# wemos_gpio.net
KiCad netlist of a schematic drawn in EAGLE
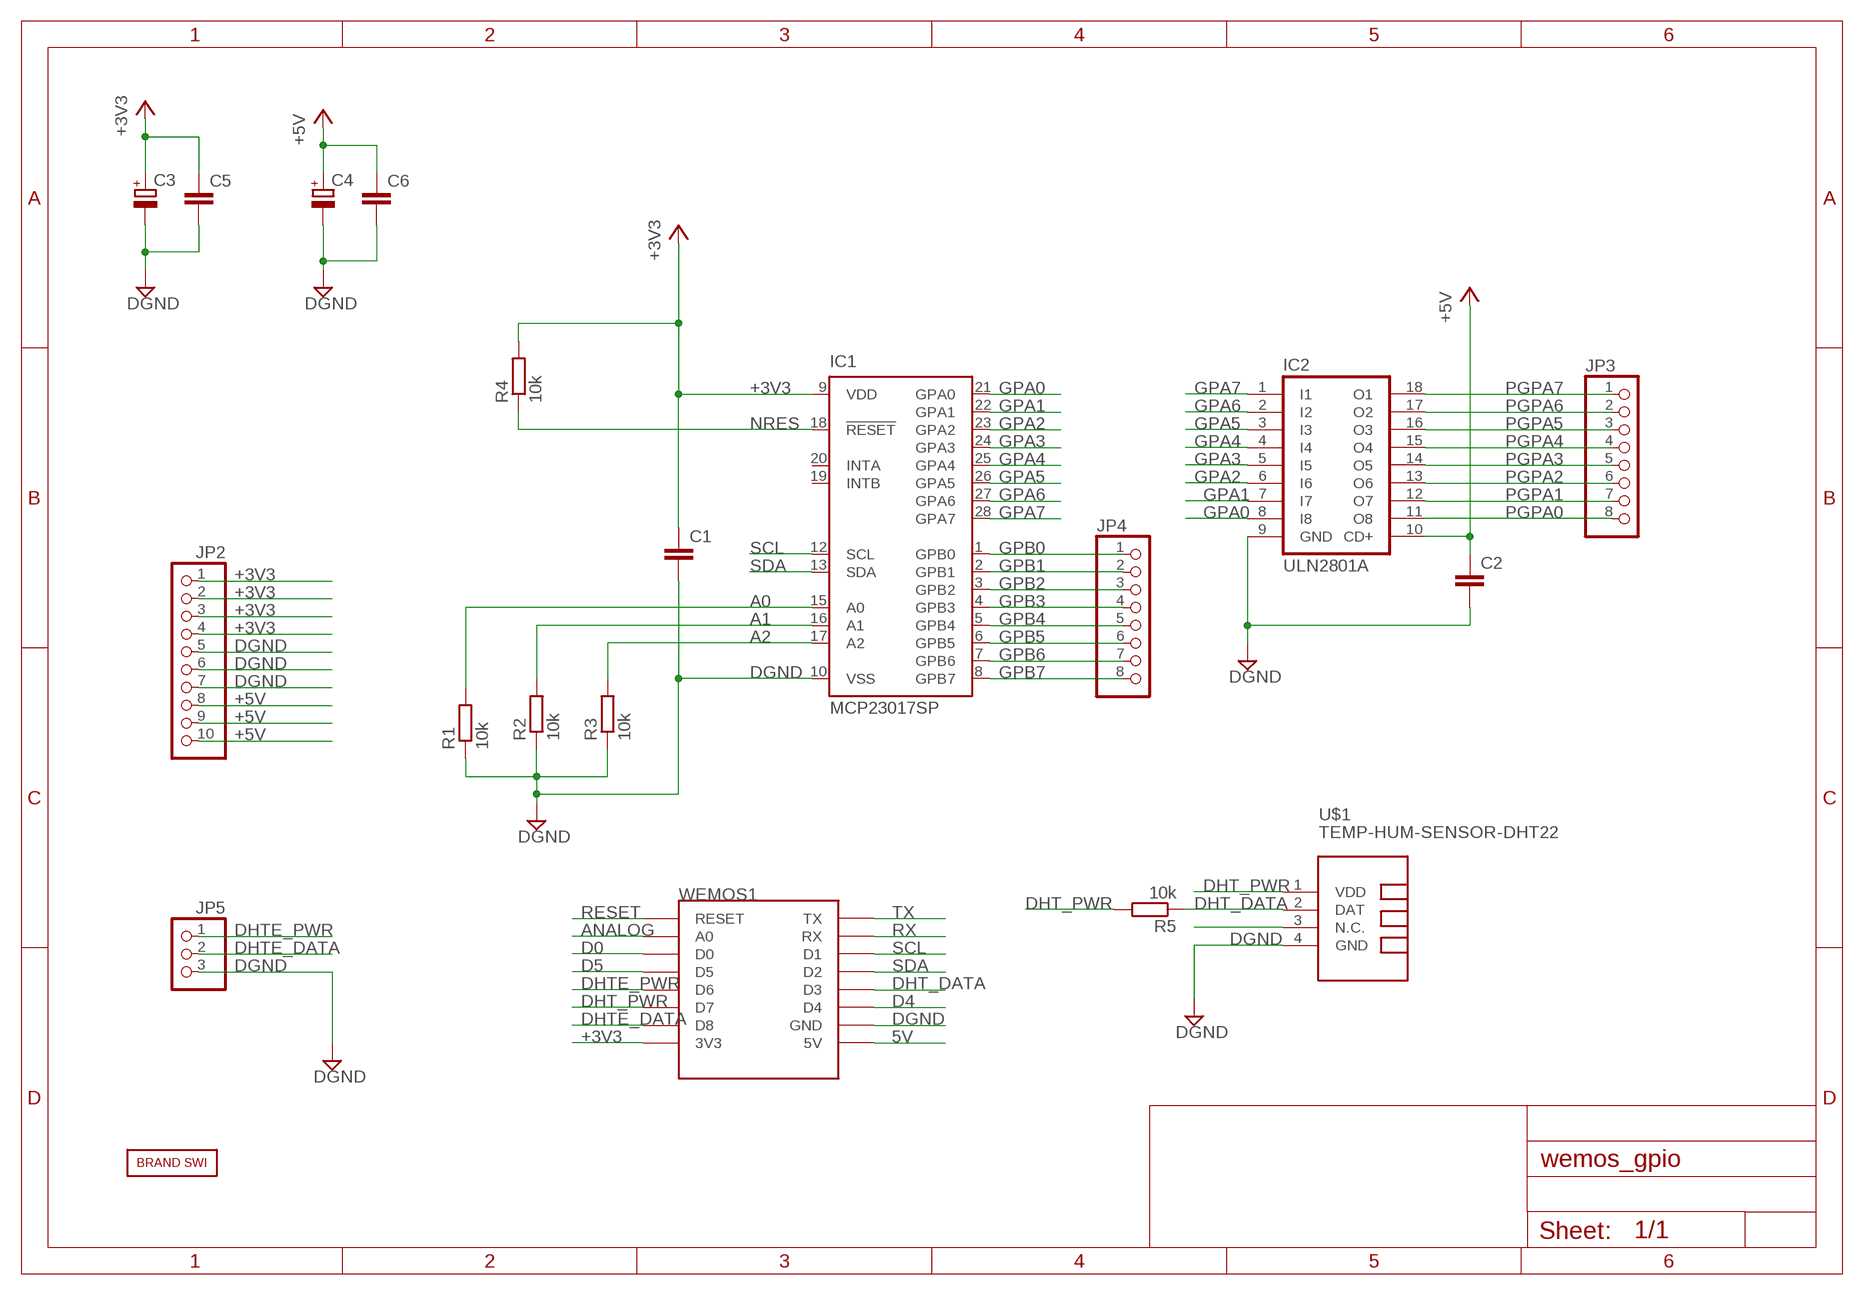
[diagram p0: schematic, sheet 1]

(export (version "E")
  (design (tool "Eeschema 10.0.6"))
  (components
    (comp (ref "C1")
      (value "C-EUC1210")
      (footprint "eagle-import:C1210")
      (libsource (lib "eagle-import") (part "C-EUC1210"))
    )
    (comp (ref "C2")
      (value "C-EUC1210")
      (footprint "eagle-import:C1210")
      (libsource (lib "eagle-import") (part "C-EUC1210"))
    )
    (comp (ref "C3")
      (value "CPOL-EUTT5D7")
      (footprint "eagle-import:TT5D7")
      (libsource (lib "eagle-import") (part "CPOL-EUTT5D7"))
    )
    (comp (ref "C4")
      (value "CPOL-EUTT5D7")
      (footprint "eagle-import:TT5D7")
      (libsource (lib "eagle-import") (part "CPOL-EUTT5D7"))
    )
    (comp (ref "C5")
      (value "C-EUC1210")
      (footprint "eagle-import:C1210")
      (libsource (lib "eagle-import") (part "C-EUC1210"))
    )
    (comp (ref "C6")
      (value "C-EUC1210")
      (footprint "eagle-import:C1210")
      (libsource (lib "eagle-import") (part "C-EUC1210"))
    )
    (comp (ref "IC1")
      (value "MCP23017SP")
      (footprint "eagle-import:DIL28-3")
      (fields (field (name "MF") "MICROCHIP") (field (name "MPN") "MCP23017-E/SP"))
      (libsource (lib "eagle-import") (part "MCP23017SP"))
    )
    (comp (ref "IC2")
      (value "ULN2801A")
      (footprint "eagle-import:DIL18")
      (libsource (lib "eagle-import") (part "ULN2801A"))
    )
    (comp (ref "JP2")
      (value "PINHD-1X10")
      (footprint "eagle-import:1X10")
      (libsource (lib "eagle-import") (part "PINHD-1X10"))
    )
    (comp (ref "JP3")
      (value "PINHD-1X8")
      (footprint "eagle-import:1X08")
      (libsource (lib "eagle-import") (part "PINHD-1X8"))
    )
    (comp (ref "JP4")
      (value "PINHD-1X8")
      (footprint "eagle-import:1X08")
      (libsource (lib "eagle-import") (part "PINHD-1X8"))
    )
    (comp (ref "JP5")
      (value "PINHD-1X3")
      (footprint "eagle-import:1X03")
      (libsource (lib "eagle-import") (part "PINHD-1X3"))
    )
    (comp (ref "R1")
      (value "10k")
      (footprint "eagle-import:M1206")
      (libsource (lib "eagle-import") (part "R-EU_M1206"))
    )
    (comp (ref "R2")
      (value "10k")
      (footprint "eagle-import:M1206")
      (libsource (lib "eagle-import") (part "R-EU_M1206"))
    )
    (comp (ref "R3")
      (value "10k")
      (footprint "eagle-import:M1206")
      (libsource (lib "eagle-import") (part "R-EU_M1206"))
    )
    (comp (ref "R4")
      (value "10k")
      (footprint "eagle-import:M1206")
      (libsource (lib "eagle-import") (part "R-EU_M1206"))
    )
    (comp (ref "R5")
      (value "10k")
      (footprint "eagle-import:M1206")
      (libsource (lib "eagle-import") (part "R-EU_M1206"))
    )
    (comp (ref "U$1")
      (value "TEMP-HUM-SENSOR-DHT22")
      (footprint "eagle-import:TEMP-HUM-SENSOR-DHT22")
      (libsource (lib "eagle-import") (part "TEMP-HUM-SENSOR-DHT22"))
    )
    (comp (ref "U$2")
      (value "BRAND_SWI5X7")
      (footprint "eagle-import:BRAND_SWI_5X7")
      (libsource (lib "eagle-import") (part "BRAND_SWI5X7"))
    )
    (comp (ref "WEMOS1")
      (value "WEMOS-D1-MINI")
      (footprint "eagle-import:WEMOS-D1-MINI")
      (libsource (lib "eagle-import") (part "WEMOS-D1-MINI"))
    )
  )
  (nets
    (net (code "1") (name "+3V3") (class "Default")
      (node (ref "C1") (pin "1") (pinfunction "1_1") (pintype "passive"))
      (node (ref "C3") (pin "+") (pinfunction "+_+") (pintype "passive"))
      (node (ref "C5") (pin "1") (pinfunction "1_1") (pintype "passive"))
      (node (ref "IC1") (pin "9") (pinfunction "VDD_9") (pintype "power_in"))
      (node (ref "JP2") (pin "1") (pinfunction "1_1") (pintype "passive"))
      (node (ref "JP2") (pin "2") (pinfunction "2_2") (pintype "passive"))
      (node (ref "JP2") (pin "3") (pinfunction "3_3") (pintype "passive"))
      (node (ref "JP2") (pin "4") (pinfunction "4_4") (pintype "passive"))
      (node (ref "R4") (pin "2") (pinfunction "2_2") (pintype "passive"))
      (node (ref "WEMOS1") (pin "3V3") (pinfunction "3V3_3V3") (pintype "bidirectional"))
    )
    (net (code "2") (name "+5V") (class "Default")
      (node (ref "C2") (pin "1") (pinfunction "1_1") (pintype "passive"))
      (node (ref "C4") (pin "+") (pinfunction "+_+") (pintype "passive"))
      (node (ref "C6") (pin "1") (pinfunction "1_1") (pintype "passive"))
      (node (ref "IC2") (pin "10") (pinfunction "CD+_10") (pintype "passive"))
      (node (ref "JP2") (pin "10") (pinfunction "10_10") (pintype "passive"))
      (node (ref "JP2") (pin "8") (pinfunction "8_8") (pintype "passive"))
      (node (ref "JP2") (pin "9") (pinfunction "9_9") (pintype "passive"))
    )
    (net (code "3") (name "/5V") (class "Default")
      (node (ref "WEMOS1") (pin "5V") (pinfunction "5V_5V") (pintype "bidirectional"))
    )
    (net (code "4") (name "/A0") (class "Default")
      (node (ref "IC1") (pin "15") (pinfunction "A0_15") (pintype "input"))
      (node (ref "R1") (pin "2") (pinfunction "2_2") (pintype "passive"))
    )
    (net (code "5") (name "/A1") (class "Default")
      (node (ref "IC1") (pin "16") (pinfunction "A1_16") (pintype "input"))
      (node (ref "R2") (pin "2") (pinfunction "2_2") (pintype "passive"))
    )
    (net (code "6") (name "/A2") (class "Default")
      (node (ref "IC1") (pin "17") (pinfunction "A2_17") (pintype "input"))
      (node (ref "R3") (pin "2") (pinfunction "2_2") (pintype "passive"))
    )
    (net (code "7") (name "/ANALOG") (class "Default")
      (node (ref "WEMOS1") (pin "A0") (pinfunction "A0_A0") (pintype "bidirectional"))
    )
    (net (code "8") (name "/D0") (class "Default")
      (node (ref "WEMOS1") (pin "D0") (pinfunction "D0_D0") (pintype "bidirectional"))
    )
    (net (code "9") (name "/D4") (class "Default")
      (node (ref "WEMOS1") (pin "D4") (pinfunction "D4_D4") (pintype "bidirectional"))
    )
    (net (code "10") (name "/D5") (class "Default")
      (node (ref "WEMOS1") (pin "D5") (pinfunction "D5_D5") (pintype "bidirectional"))
    )
    (net (code "11") (name "/DHTE_DATA") (class "Default")
      (node (ref "JP5") (pin "2") (pinfunction "2_2") (pintype "passive"))
      (node (ref "WEMOS1") (pin "D8") (pinfunction "D8_D8") (pintype "bidirectional"))
    )
    (net (code "12") (name "/DHTE_PWR") (class "Default")
      (node (ref "JP5") (pin "1") (pinfunction "1_1") (pintype "passive"))
      (node (ref "WEMOS1") (pin "D6") (pinfunction "D6_D6") (pintype "bidirectional"))
    )
    (net (code "13") (name "/DHT_DATA") (class "Default")
      (node (ref "R5") (pin "1") (pinfunction "1_1") (pintype "passive"))
      (node (ref "U$1") (pin "2") (pinfunction "DAT_2") (pintype "bidirectional"))
      (node (ref "WEMOS1") (pin "D3") (pinfunction "D3_D3") (pintype "bidirectional"))
    )
    (net (code "14") (name "/DHT_PWR") (class "Default")
      (node (ref "R5") (pin "2") (pinfunction "2_2") (pintype "passive"))
      (node (ref "U$1") (pin "1") (pinfunction "VDD_1") (pintype "power_in"))
      (node (ref "WEMOS1") (pin "D7") (pinfunction "D7_D7") (pintype "bidirectional"))
    )
    (net (code "15") (name "/GPA0") (class "Default")
      (node (ref "IC1") (pin "21") (pinfunction "GPA0_21") (pintype "bidirectional"))
      (node (ref "IC2") (pin "8") (pinfunction "I8_8") (pintype "input"))
    )
    (net (code "16") (name "/GPA1") (class "Default")
      (node (ref "IC1") (pin "22") (pinfunction "GPA1_22") (pintype "bidirectional"))
      (node (ref "IC2") (pin "7") (pinfunction "I7_7") (pintype "input"))
    )
    (net (code "17") (name "/GPA2") (class "Default")
      (node (ref "IC1") (pin "23") (pinfunction "GPA2_23") (pintype "bidirectional"))
      (node (ref "IC2") (pin "6") (pinfunction "I6_6") (pintype "input"))
    )
    (net (code "18") (name "/GPA3") (class "Default")
      (node (ref "IC1") (pin "24") (pinfunction "GPA3_24") (pintype "bidirectional"))
      (node (ref "IC2") (pin "5") (pinfunction "I5_5") (pintype "input"))
    )
    (net (code "19") (name "/GPA4") (class "Default")
      (node (ref "IC1") (pin "25") (pinfunction "GPA4_25") (pintype "bidirectional"))
      (node (ref "IC2") (pin "4") (pinfunction "I4_4") (pintype "input"))
    )
    (net (code "20") (name "/GPA5") (class "Default")
      (node (ref "IC1") (pin "26") (pinfunction "GPA5_26") (pintype "bidirectional"))
      (node (ref "IC2") (pin "3") (pinfunction "I3_3") (pintype "input"))
    )
    (net (code "21") (name "/GPA6") (class "Default")
      (node (ref "IC1") (pin "27") (pinfunction "GPA6_27") (pintype "bidirectional"))
      (node (ref "IC2") (pin "2") (pinfunction "I2_2") (pintype "input"))
    )
    (net (code "22") (name "/GPA7") (class "Default")
      (node (ref "IC1") (pin "28") (pinfunction "GPA7_28") (pintype "bidirectional"))
      (node (ref "IC2") (pin "1") (pinfunction "I1_1") (pintype "input"))
    )
    (net (code "23") (name "/GPB0") (class "Default")
      (node (ref "IC1") (pin "1") (pinfunction "GPB0_1") (pintype "bidirectional"))
      (node (ref "JP4") (pin "1") (pinfunction "1_1") (pintype "passive"))
    )
    (net (code "24") (name "/GPB1") (class "Default")
      (node (ref "IC1") (pin "2") (pinfunction "GPB1_2") (pintype "bidirectional"))
      (node (ref "JP4") (pin "2") (pinfunction "2_2") (pintype "passive"))
    )
    (net (code "25") (name "/GPB2") (class "Default")
      (node (ref "IC1") (pin "3") (pinfunction "GPB2_3") (pintype "bidirectional"))
      (node (ref "JP4") (pin "3") (pinfunction "3_3") (pintype "passive"))
    )
    (net (code "26") (name "/GPB3") (class "Default")
      (node (ref "IC1") (pin "4") (pinfunction "GPB3_4") (pintype "bidirectional"))
      (node (ref "JP4") (pin "4") (pinfunction "4_4") (pintype "passive"))
    )
    (net (code "27") (name "/GPB4") (class "Default")
      (node (ref "IC1") (pin "5") (pinfunction "GPB4_5") (pintype "bidirectional"))
      (node (ref "JP4") (pin "5") (pinfunction "5_5") (pintype "passive"))
    )
    (net (code "28") (name "/GPB5") (class "Default")
      (node (ref "IC1") (pin "6") (pinfunction "GPB5_6") (pintype "bidirectional"))
      (node (ref "JP4") (pin "6") (pinfunction "6_6") (pintype "passive"))
    )
    (net (code "29") (name "/GPB6") (class "Default")
      (node (ref "IC1") (pin "7") (pinfunction "GPB6_7") (pintype "bidirectional"))
      (node (ref "JP4") (pin "7") (pinfunction "7_7") (pintype "passive"))
    )
    (net (code "30") (name "/GPB7") (class "Default")
      (node (ref "IC1") (pin "8") (pinfunction "GPB7_8") (pintype "bidirectional"))
      (node (ref "JP4") (pin "8") (pinfunction "8_8") (pintype "passive"))
    )
    (net (code "31") (name "/NRES") (class "Default")
      (node (ref "IC1") (pin "18") (pinfunction "~{RESET}_18") (pintype "input"))
      (node (ref "R4") (pin "1") (pinfunction "1_1") (pintype "passive"))
    )
    (net (code "32") (name "/PGPA0") (class "Default")
      (node (ref "IC2") (pin "11") (pinfunction "O8_11") (pintype "open_collector"))
      (node (ref "JP3") (pin "8") (pinfunction "8_8") (pintype "passive"))
    )
    (net (code "33") (name "/PGPA1") (class "Default")
      (node (ref "IC2") (pin "12") (pinfunction "O7_12") (pintype "open_collector"))
      (node (ref "JP3") (pin "7") (pinfunction "7_7") (pintype "passive"))
    )
    (net (code "34") (name "/PGPA2") (class "Default")
      (node (ref "IC2") (pin "13") (pinfunction "O6_13") (pintype "open_collector"))
      (node (ref "JP3") (pin "6") (pinfunction "6_6") (pintype "passive"))
    )
    (net (code "35") (name "/PGPA3") (class "Default")
      (node (ref "IC2") (pin "14") (pinfunction "O5_14") (pintype "open_collector"))
      (node (ref "JP3") (pin "5") (pinfunction "5_5") (pintype "passive"))
    )
    (net (code "36") (name "/PGPA4") (class "Default")
      (node (ref "IC2") (pin "15") (pinfunction "O4_15") (pintype "open_collector"))
      (node (ref "JP3") (pin "4") (pinfunction "4_4") (pintype "passive"))
    )
    (net (code "37") (name "/PGPA5") (class "Default")
      (node (ref "IC2") (pin "16") (pinfunction "O3_16") (pintype "open_collector"))
      (node (ref "JP3") (pin "3") (pinfunction "3_3") (pintype "passive"))
    )
    (net (code "38") (name "/PGPA6") (class "Default")
      (node (ref "IC2") (pin "17") (pinfunction "O2_17") (pintype "open_collector"))
      (node (ref "JP3") (pin "2") (pinfunction "2_2") (pintype "passive"))
    )
    (net (code "39") (name "/PGPA7") (class "Default")
      (node (ref "IC2") (pin "18") (pinfunction "O1_18") (pintype "open_collector"))
      (node (ref "JP3") (pin "1") (pinfunction "1_1") (pintype "passive"))
    )
    (net (code "40") (name "/RESET") (class "Default")
      (node (ref "WEMOS1") (pin "RESET") (pinfunction "RESET_RESET") (pintype "bidirectional"))
    )
    (net (code "41") (name "/RX") (class "Default")
      (node (ref "WEMOS1") (pin "RX") (pinfunction "RX_RX") (pintype "bidirectional"))
    )
    (net (code "42") (name "/SCL") (class "Default")
      (node (ref "IC1") (pin "12") (pinfunction "SCL_12") (pintype "input"))
      (node (ref "WEMOS1") (pin "D1") (pinfunction "D1_D1") (pintype "bidirectional"))
    )
    (net (code "43") (name "/SDA") (class "Default")
      (node (ref "IC1") (pin "13") (pinfunction "SDA_13") (pintype "bidirectional"))
      (node (ref "WEMOS1") (pin "D2") (pinfunction "D2_D2") (pintype "bidirectional"))
    )
    (net (code "44") (name "/TX") (class "Default")
      (node (ref "WEMOS1") (pin "TX") (pinfunction "TX_TX") (pintype "bidirectional"))
    )
    (net (code "45") (name "DGND") (class "Default")
      (node (ref "C1") (pin "2") (pinfunction "2_2") (pintype "passive"))
      (node (ref "C2") (pin "2") (pinfunction "2_2") (pintype "passive"))
      (node (ref "C3") (pin "-") (pinfunction "-_-") (pintype "passive"))
      (node (ref "C4") (pin "-") (pinfunction "-_-") (pintype "passive"))
      (node (ref "C5") (pin "2") (pinfunction "2_2") (pintype "passive"))
      (node (ref "C6") (pin "2") (pinfunction "2_2") (pintype "passive"))
      (node (ref "IC1") (pin "10") (pinfunction "VSS_10") (pintype "power_in"))
      (node (ref "IC2") (pin "9") (pinfunction "GND_9") (pintype "power_in"))
      (node (ref "JP2") (pin "5") (pinfunction "5_5") (pintype "passive"))
      (node (ref "JP2") (pin "6") (pinfunction "6_6") (pintype "passive"))
      (node (ref "JP2") (pin "7") (pinfunction "7_7") (pintype "passive"))
      (node (ref "JP5") (pin "3") (pinfunction "3_3") (pintype "passive"))
      (node (ref "R1") (pin "1") (pinfunction "1_1") (pintype "passive"))
      (node (ref "R2") (pin "1") (pinfunction "1_1") (pintype "passive"))
      (node (ref "R3") (pin "1") (pinfunction "1_1") (pintype "passive"))
      (node (ref "U$1") (pin "4") (pinfunction "GND_4") (pintype "power_in"))
      (node (ref "WEMOS1") (pin "GND") (pinfunction "GND_GND") (pintype "bidirectional"))
    )
    (net (code "46") (name "unconnected-(IC1-INTA-Pad20)") (class "Default")
      (node (ref "IC1") (pin "20") (pinfunction "INTA_20") (pintype "output"))
    )
    (net (code "47") (name "unconnected-(IC1-INTB-Pad19)") (class "Default")
      (node (ref "IC1") (pin "19") (pinfunction "INTB_19") (pintype "output"))
    )
    (net (code "48") (name "unconnected-(U$1-N.C.-Pad3)") (class "Default")
      (node (ref "U$1") (pin "3") (pinfunction "N.C._3") (pintype "passive"))
    )
  )
)
